# 22-CAN.net
KiCad netlist of a schematic drawn in Altium Designer
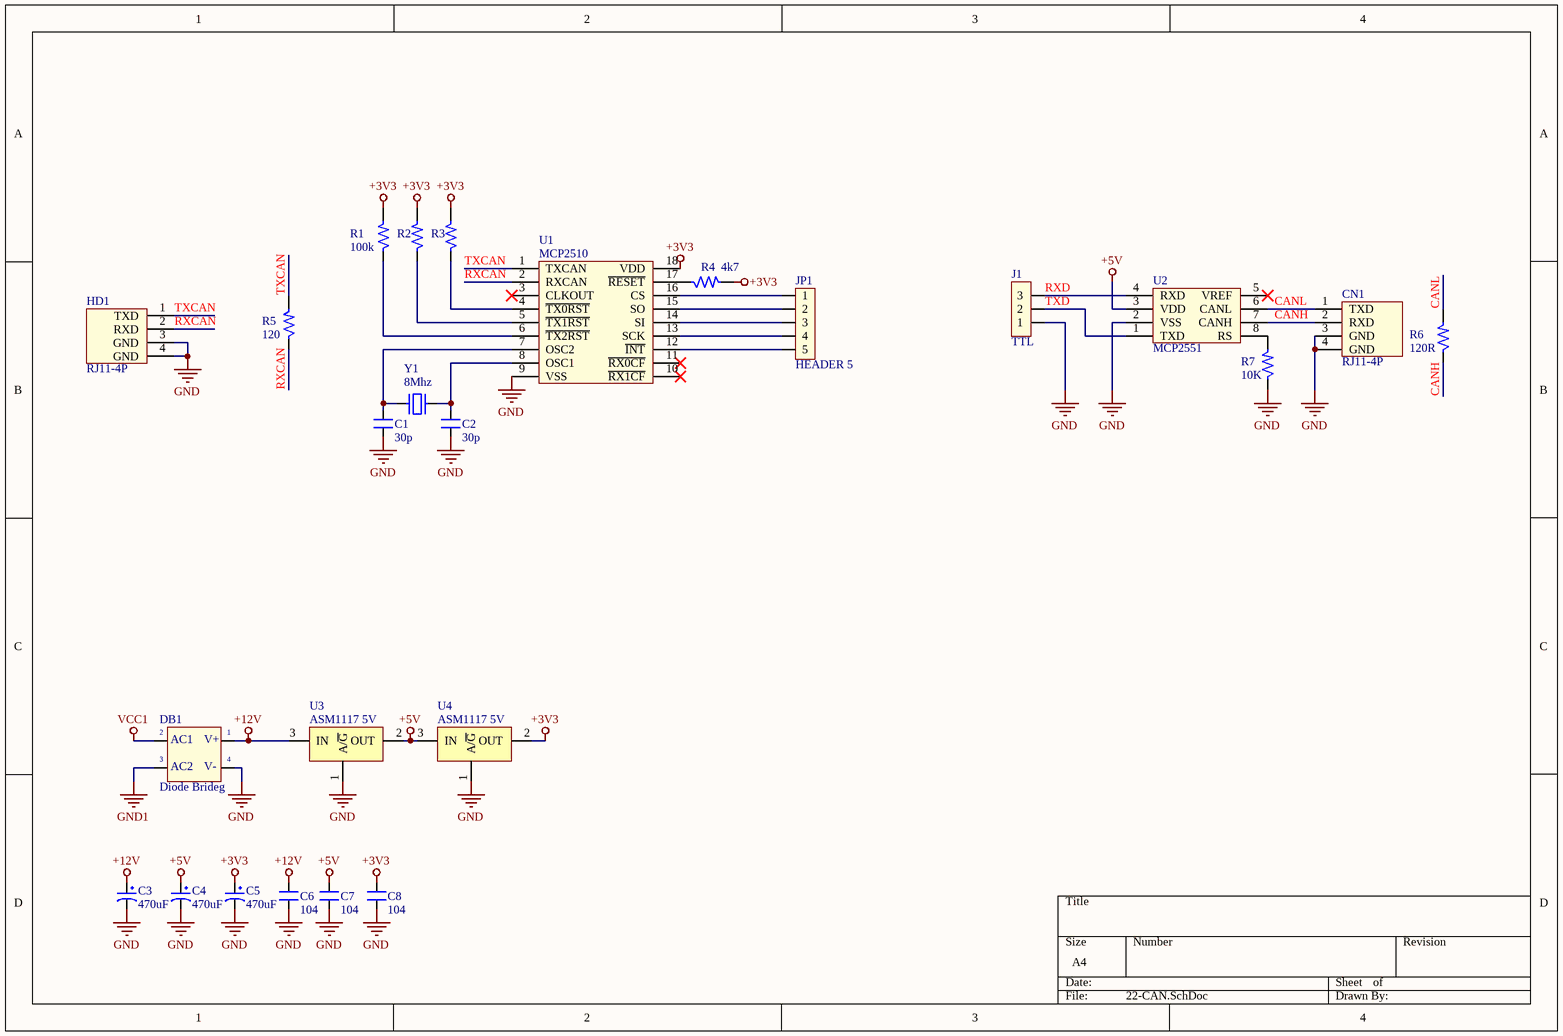
[diagram p0: 22-CAN.SchDoc]

(export (version "E")
  (design (tool "Eeschema 10.0.6"))
  (components
    (comp (ref "C1")
      (value "30p")
      (footprint "C-0805")
      (fields (field (name "DESIGNED BY") "VanDungEvn"))
      (libsource (lib "syhaunguyen") (part "CN"))
    )
    (comp (ref "C2")
      (value "30p")
      (footprint "C-0805")
      (fields (field (name "DESIGNED BY") "VanDungEvn"))
      (libsource (lib "syhaunguyen") (part "CN"))
    )
    (comp (ref "C3")
      (value "470uF")
      (footprint "C-ALU-D6.5")
      (description "Cap P  0,1uF < 22uF , 16 - 50V")
      (libsource (lib "PART") (part "CP1"))
    )
    (comp (ref "C4")
      (value "470uF")
      (footprint "C-ALU-D6.5")
      (description "Cap P  0,1uF < 22uF , 16 - 50V")
      (libsource (lib "PART") (part "CP1"))
    )
    (comp (ref "C5")
      (value "470uF")
      (footprint "C-ALU-D6.5")
      (description "Cap P  0,1uF < 22uF , 16 - 50V")
      (libsource (lib "PART") (part "CP1"))
    )
    (comp (ref "C6")
      (value "104")
      (footprint "C-0805")
      (fields (field (name "DESIGNED BY") "VanDungEvn"))
      (libsource (lib "syhaunguyen") (part "CN"))
    )
    (comp (ref "C7")
      (value "104")
      (footprint "C-0805")
      (fields (field (name "DESIGNED BY") "VanDungEvn"))
      (libsource (lib "syhaunguyen") (part "CN"))
    )
    (comp (ref "C8")
      (value "104")
      (footprint "C-0805")
      (fields (field (name "DESIGNED BY") "VanDungEvn"))
      (libsource (lib "syhaunguyen") (part "CN"))
    )
    (comp (ref "CN1") (value "RJ11-4P") (libsource (lib "") (part "RJ11-4P_1")))
    (comp (ref "DB1")
      (value "Diode Brideg")
      (footprint "D-DB-1A-SMD")
      (description "Convert AC to DC voltage, 4 pin")
      (libsource (lib "PART") (part "DB"))
    )
    (comp (ref "HD1") (value "RJ11-4P") (libsource (lib "doAnTotNghiep2017Lib") (part "RJ11-4P")))
    (comp (ref "J1")
      (value "TTL")
      (footprint "JP3")
      (description "Jumper 3")
      (libsource (lib "syhaunguyen") (part "JP3"))
    )
    (comp (ref "JP1") (value "HEADER 5") (footprint "JP5") (libsource (lib "syhaunguyen") (part "JP5")))
    (comp (ref "R1")
      (value "100k")
      (footprint "R-0805")
      (description "Resistor 1/4W")
      (libsource (lib "PART") (part "R"))
    )
    (comp (ref "R2")
      (value "100k")
      (footprint "R-0805")
      (description "Resistor 1/4W")
      (libsource (lib "PART") (part "R"))
    )
    (comp (ref "R3")
      (value "100k")
      (footprint "R-0805")
      (description "Resistor 1/4W")
      (libsource (lib "PART") (part "R"))
    )
    (comp (ref "R4")
      (value "4k7")
      (footprint "R-0805")
      (description "Resistor 1/4W")
      (libsource (lib "PART") (part "R"))
    )
    (comp (ref "R5")
      (value "120")
      (footprint "R-0805")
      (description "Resistor 1/4W")
      (libsource (lib "syhaunguyen") (part "R"))
    )
    (comp (ref "R6")
      (value "120R")
      (footprint "R-0805")
      (description "Resistor 1/4W")
      (libsource (lib "syhaunguyen") (part "R"))
    )
    (comp (ref "R7")
      (value "10K")
      (footprint "R-0805")
      (description "Resistor 1/4W")
      (libsource (lib "syhaunguyen") (part "R"))
    )
    (comp (ref "U1")
      (value "MCP2510")
      (footprint "SOIC-18-W")
      (libsource (lib "doAnTotNghiep2017Lib") (part "MCP2510"))
    )
    (comp (ref "U2")
      (value "MCP2551")
      (footprint "SOIC-8")
      (libsource (lib "doAnTotNghiep2017Lib") (part "MCP2551"))
    )
    (comp (ref "U3")
      (value "ASM1117 5V")
      (footprint "TO-252")
      (libsource (lib "doAnTotNghiep2017Lib") (part "ASM1117"))
    )
    (comp (ref "U4")
      (value "ASM1117 5V")
      (footprint "TO-252")
      (libsource (lib "doAnTotNghiep2017Lib") (part "ASM1117"))
    )
    (comp (ref "Y1")
      (value "8Mhz")
      (footprint "XTAL-AB38T-SMD")
      (libsource (lib "hoangvanhuynh") (part "XTAL"))
    )
  )
  (nets
    (net (code "1") (name "+3V3") (class "Default")
      (node (ref "C5") (pin "1") (pinfunction "1_1") (pintype "passive"))
      (node (ref "C8") (pin "2") (pinfunction "2_2") (pintype "passive"))
      (node (ref "R1") (pin "2") (pinfunction "2_2") (pintype "passive"))
      (node (ref "R2") (pin "2") (pinfunction "2_2") (pintype "passive"))
      (node (ref "R3") (pin "2") (pinfunction "2_2") (pintype "passive"))
      (node (ref "R4") (pin "2") (pinfunction "2_2") (pintype "passive"))
      (node (ref "U1") (pin "18") (pinfunction "VDD_18") (pintype "passive"))
      (node (ref "U4") (pin "2") (pinfunction "OUT_2") (pintype "passive"))
    )
    (net (code "2") (name "+5V") (class "Default")
      (node (ref "C4") (pin "1") (pinfunction "1_1") (pintype "passive"))
      (node (ref "C7") (pin "2") (pinfunction "2_2") (pintype "passive"))
      (node (ref "U2") (pin "3") (pinfunction "VDD_3") (pintype "passive"))
      (node (ref "U3") (pin "2") (pinfunction "OUT_2") (pintype "passive"))
      (node (ref "U4") (pin "3") (pinfunction "IN_3") (pintype "passive"))
    )
    (net (code "3") (name "+12V") (class "Default")
      (node (ref "C3") (pin "1") (pinfunction "1_1") (pintype "passive"))
      (node (ref "C6") (pin "2") (pinfunction "2_2") (pintype "passive"))
      (node (ref "DB1") (pin "3") (pinfunction "AC2_3") (pintype "passive"))
      (node (ref "U3") (pin "3") (pinfunction "IN_3") (pintype "passive"))
    )
    (net (code "4") (name "/CANH") (class "Default")
      (node (ref "CN1") (pin "2") (pinfunction "RXD_2") (pintype "passive"))
      (node (ref "R6") (pin "1") (pinfunction "1_1") (pintype "passive"))
      (node (ref "U2") (pin "7") (pinfunction "CANH_7") (pintype "passive"))
    )
    (net (code "5") (name "/CANL") (class "Default")
      (node (ref "CN1") (pin "1") (pinfunction "TXD_1") (pintype "passive"))
      (node (ref "R6") (pin "2") (pinfunction "2_2") (pintype "passive"))
      (node (ref "U2") (pin "6") (pinfunction "CANL_6") (pintype "passive"))
    )
    (net (code "6") (name "/RXCAN") (class "Default")
      (node (ref "HD1") (pin "2") (pinfunction "RXD_2") (pintype "passive"))
      (node (ref "R5") (pin "1") (pinfunction "1_1") (pintype "passive"))
      (node (ref "U1") (pin "2") (pinfunction "RXCAN_2") (pintype "passive"))
    )
    (net (code "7") (name "/RXD") (class "Default")
      (node (ref "J1") (pin "3") (pinfunction "3_3") (pintype "passive"))
      (node (ref "U2") (pin "4") (pinfunction "RXD_4") (pintype "passive"))
    )
    (net (code "8") (name "/TXCAN") (class "Default")
      (node (ref "HD1") (pin "1") (pinfunction "TXD_1") (pintype "passive"))
      (node (ref "R5") (pin "2") (pinfunction "2_2") (pintype "passive"))
      (node (ref "U1") (pin "1") (pinfunction "TXCAN_1") (pintype "passive"))
    )
    (net (code "9") (name "/TXD") (class "Default")
      (node (ref "J1") (pin "2") (pinfunction "2_2") (pintype "passive"))
      (node (ref "U2") (pin "1") (pinfunction "TXD_1") (pintype "passive"))
    )
    (net (code "10") (name "GND") (class "Default")
      (node (ref "C1") (pin "1") (pinfunction "1_1") (pintype "passive"))
      (node (ref "C2") (pin "1") (pinfunction "1_1") (pintype "passive"))
      (node (ref "C3") (pin "2") (pinfunction "2_2") (pintype "passive"))
      (node (ref "C4") (pin "2") (pinfunction "2_2") (pintype "passive"))
      (node (ref "C5") (pin "2") (pinfunction "2_2") (pintype "passive"))
      (node (ref "C6") (pin "1") (pinfunction "1_1") (pintype "passive"))
      (node (ref "C7") (pin "1") (pinfunction "1_1") (pintype "passive"))
      (node (ref "C8") (pin "1") (pinfunction "1_1") (pintype "passive"))
      (node (ref "CN1") (pin "3") (pinfunction "GND_3") (pintype "passive"))
      (node (ref "CN1") (pin "4") (pinfunction "GND_4") (pintype "passive"))
      (node (ref "DB1") (pin "4") (pinfunction "-V_OUT_4") (pintype "passive"))
      (node (ref "HD1") (pin "3") (pinfunction "GND_3") (pintype "passive"))
      (node (ref "HD1") (pin "4") (pinfunction "GND_4") (pintype "passive"))
      (node (ref "J1") (pin "1") (pinfunction "1_1") (pintype "passive"))
      (node (ref "R7") (pin "1") (pinfunction "1_1") (pintype "passive"))
      (node (ref "U1") (pin "9") (pinfunction "VSS_9") (pintype "passive"))
      (node (ref "U2") (pin "2") (pinfunction "VSS_2") (pintype "passive"))
      (node (ref "U3") (pin "1") (pinfunction "A/~{G}_1") (pintype "passive"))
      (node (ref "U4") (pin "1") (pinfunction "A/~{G}_1") (pintype "passive"))
    )
    (net (code "11") (name "GND1") (class "Default")
      (node (ref "DB1") (pin "1") (pinfunction "+V_OUT_1") (pintype "passive"))
    )
    (net (code "12") (name "Net-(U1-CS)") (class "Default")
      (node (ref "JP1") (pin "1") (pinfunction "1_1") (pintype "passive"))
      (node (ref "U1") (pin "16") (pinfunction "CS_16") (pintype "passive"))
    )
    (net (code "13") (name "Net-(U1-OSC1)") (class "Default")
      (node (ref "C2") (pin "2") (pinfunction "2_2") (pintype "passive"))
      (node (ref "U1") (pin "8") (pinfunction "OSC1_8") (pintype "passive"))
      (node (ref "Y1") (pin "2") (pinfunction "2_2") (pintype "passive"))
    )
    (net (code "14") (name "Net-(U1-OSC2)") (class "Default")
      (node (ref "C1") (pin "2") (pinfunction "2_2") (pintype "passive"))
      (node (ref "U1") (pin "7") (pinfunction "OSC2_7") (pintype "passive"))
      (node (ref "Y1") (pin "1") (pinfunction "1_1") (pintype "passive"))
    )
    (net (code "15") (name "Net-(U1-SCK)") (class "Default")
      (node (ref "JP1") (pin "4") (pinfunction "4_4") (pintype "passive"))
      (node (ref "U1") (pin "13") (pinfunction "SCK_13") (pintype "passive"))
    )
    (net (code "16") (name "Net-(U1-SI)") (class "Default")
      (node (ref "JP1") (pin "3") (pinfunction "3_3") (pintype "passive"))
      (node (ref "U1") (pin "14") (pinfunction "SI_14") (pintype "passive"))
    )
    (net (code "17") (name "Net-(U1-SO)") (class "Default")
      (node (ref "JP1") (pin "2") (pinfunction "2_2") (pintype "passive"))
      (node (ref "U1") (pin "15") (pinfunction "SO_15") (pintype "passive"))
    )
    (net (code "18") (name "Net-(U1-~{INT})") (class "Default")
      (node (ref "JP1") (pin "5") (pinfunction "5_5") (pintype "passive"))
      (node (ref "U1") (pin "12") (pinfunction "~{INT}_12") (pintype "passive"))
    )
    (net (code "19") (name "Net-(U1-~{RESET})") (class "Default")
      (node (ref "R4") (pin "1") (pinfunction "1_1") (pintype "passive"))
      (node (ref "U1") (pin "17") (pinfunction "~{RESET}_17") (pintype "passive"))
    )
    (net (code "20") (name "Net-(U1-~{TX0RST})") (class "Default")
      (node (ref "R3") (pin "1") (pinfunction "1_1") (pintype "passive"))
      (node (ref "U1") (pin "4") (pinfunction "~{TX0RST}_4") (pintype "passive"))
    )
    (net (code "21") (name "Net-(U1-~{TX1RST})") (class "Default")
      (node (ref "R2") (pin "1") (pinfunction "1_1") (pintype "passive"))
      (node (ref "U1") (pin "5") (pinfunction "~{TX1RST}_5") (pintype "passive"))
    )
    (net (code "22") (name "Net-(U1-~{TX2RST})") (class "Default")
      (node (ref "R1") (pin "1") (pinfunction "1_1") (pintype "passive"))
      (node (ref "U1") (pin "6") (pinfunction "~{TX2RST}_6") (pintype "passive"))
    )
    (net (code "23") (name "Net-(U2-RS)") (class "Default")
      (node (ref "R7") (pin "2") (pinfunction "2_2") (pintype "passive"))
      (node (ref "U2") (pin "8") (pinfunction "RS_8") (pintype "passive"))
    )
    (net (code "24") (name "VCC1") (class "Default")
      (node (ref "DB1") (pin "2") (pinfunction "AC1_2") (pintype "passive"))
    )
    (net (code "25") (name "unconnected-(U1-CLKOUT-Pad3)") (class "Default")
      (node (ref "U1") (pin "3") (pinfunction "CLKOUT_3") (pintype "passive+no_connect"))
    )
    (net (code "26") (name "unconnected-(U1-~{RX0CF}-Pad11)") (class "Default")
      (node (ref "U1") (pin "11") (pinfunction "~{RX0CF}_11") (pintype "passive+no_connect"))
    )
    (net (code "27") (name "unconnected-(U1-~{RX1CF}-Pad10)") (class "Default")
      (node (ref "U1") (pin "10") (pinfunction "~{RX1CF}_10") (pintype "passive+no_connect"))
    )
    (net (code "28") (name "unconnected-(U2-VREF-Pad5)") (class "Default")
      (node (ref "U2") (pin "5") (pinfunction "VREF_5") (pintype "passive+no_connect"))
    )
  )
)
